# RP2350.net
KiCad netlist of a schematic drawn in Altium Designer
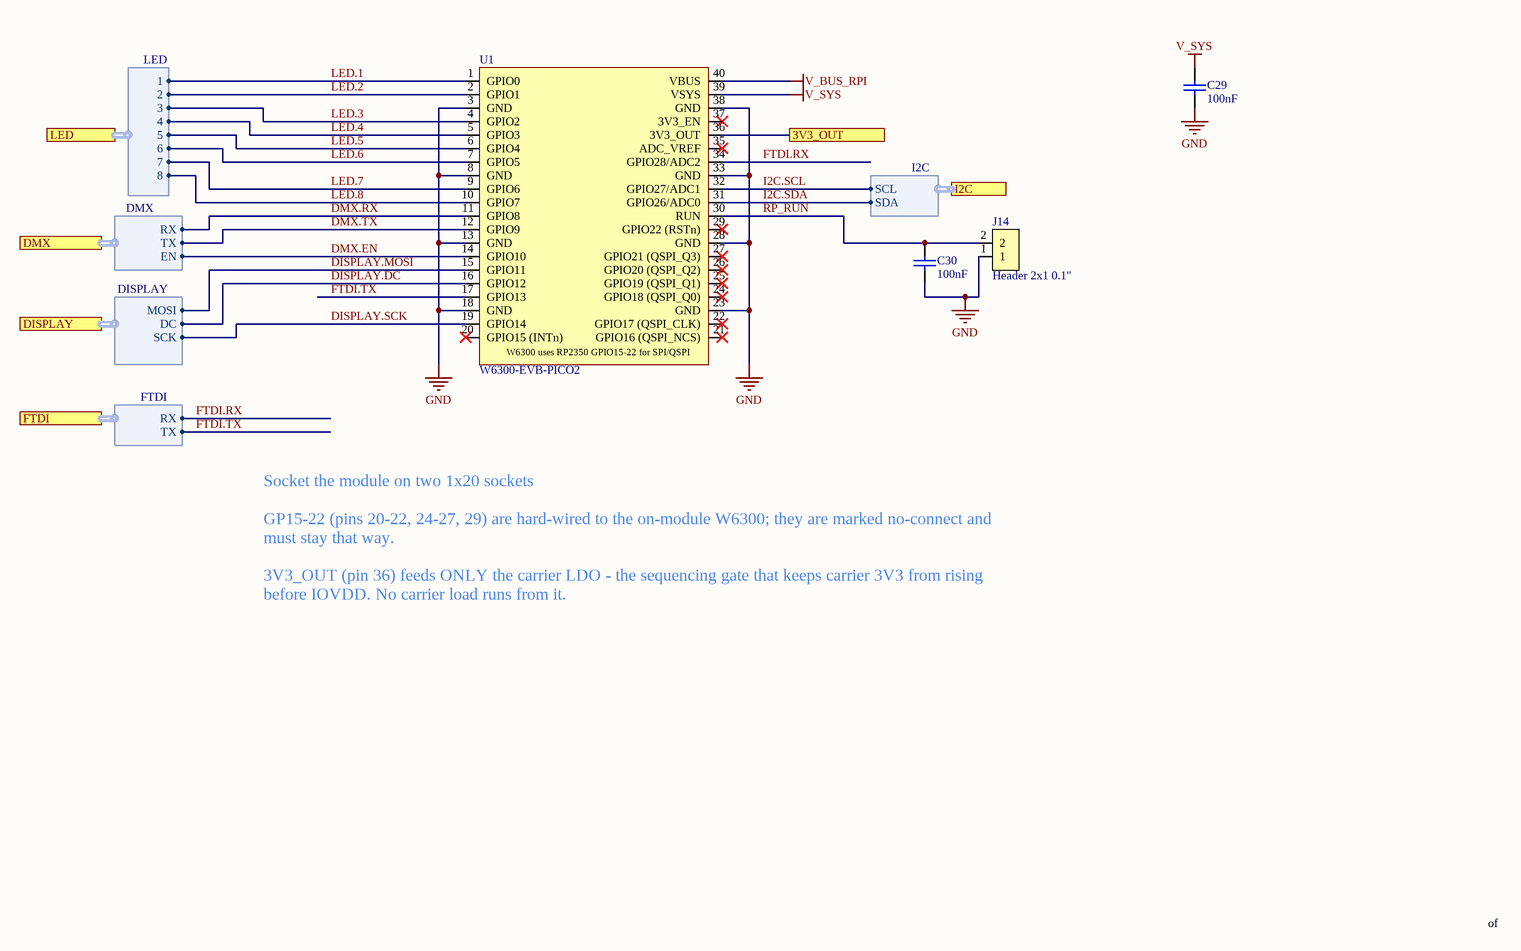
[diagram p0: RP2350.SchDoc]

(export (version "E")
  (design (tool "Eeschema 10.0.6"))
  (components
    (comp (ref "C29")
      (value "100nF")
      (footprint "CAPC1608X10N_0603_MED")
      (fields (field (name "Comment") "CC0603KRX7R0BB104"))
      (libsource (lib "Equus Computer Systems") (part "CAP-NP-2"))
    )
    (comp (ref "C30")
      (value "100nF")
      (footprint "CAPC1608X10N_0603_MED")
      (fields (field (name "Comment") "CC0603KRX7R0BB104"))
      (libsource (lib "Equus Computer Systems") (part "CAP-NP-2"))
    )
    (comp (ref "J14")
      (value "Header 2x1 0.1\"")
      (footprint "FP-M20-9990245-MFG")
      (description "Conn Header Vert 2POS 2.54MM")
      (libsource (lib "Equus Computer Systems") (part "HEADER-2x1"))
    )
    (comp (ref "U1")
      (value "W6300-EVB-PICO2")
      (footprint "W6300-EVB-PICO2_0.4375_standoff")
      (description "Raspberry Pi RP2350 and fully hardwired TCP/IP controller W6300")
      (libsource (lib "Equus Computer Systems") (part "W6300-EVB-PICO2"))
    )
  )
  (nets
    (net (code "6") (name "/3V3_OUT") (class "Default")
      (node (ref "U1") (pin "36") (pinfunction "3V3_OUT_36") (pintype "passive"))
    )
    (net (code "7") (name "/DISPLAY.DC") (class "Default")
      (node (ref "U1") (pin "16") (pinfunction "GPIO12_16") (pintype "passive"))
    )
    (net (code "8") (name "/DISPLAY.MOSI") (class "Default")
      (node (ref "U1") (pin "15") (pinfunction "GPIO11_15") (pintype "passive"))
    )
    (net (code "9") (name "/DISPLAY.SCK") (class "Default")
      (node (ref "U1") (pin "19") (pinfunction "GPIO14_19") (pintype "passive"))
    )
    (net (code "10") (name "/DMX.EN") (class "Default")
      (node (ref "U1") (pin "14") (pinfunction "GPIO10_14") (pintype "passive"))
    )
    (net (code "11") (name "/DMX.RX") (class "Default")
      (node (ref "U1") (pin "11") (pinfunction "GPIO8_11") (pintype "passive"))
    )
    (net (code "12") (name "/DMX.TX") (class "Default")
      (node (ref "U1") (pin "12") (pinfunction "GPIO9_12") (pintype "passive"))
    )
    (net (code "13") (name "/FTDI.RX") (class "Default")
      (node (ref "U1") (pin "34") (pinfunction "GPIO28/ADC2_34") (pintype "passive"))
    )
    (net (code "14") (name "/FTDI.TX") (class "Default")
      (node (ref "U1") (pin "17") (pinfunction "GPIO13_17") (pintype "passive"))
    )
    (net (code "15") (name "/I2C.SCL") (class "Default")
      (node (ref "U1") (pin "32") (pinfunction "GPIO27/ADC1_32") (pintype "passive"))
    )
    (net (code "16") (name "/I2C.SDA") (class "Default")
      (node (ref "U1") (pin "31") (pinfunction "GPIO26/ADC0_31") (pintype "passive"))
    )
    (net (code "17") (name "/LED.1") (class "Default")
      (node (ref "U1") (pin "1") (pinfunction "GPIO0_1") (pintype "passive"))
    )
    (net (code "18") (name "/LED.2") (class "Default")
      (node (ref "U1") (pin "2") (pinfunction "GPIO1_2") (pintype "passive"))
    )
    (net (code "19") (name "/LED.3") (class "Default")
      (node (ref "U1") (pin "4") (pinfunction "GPIO2_4") (pintype "passive"))
    )
    (net (code "20") (name "/LED.4") (class "Default")
      (node (ref "U1") (pin "5") (pinfunction "GPIO3_5") (pintype "passive"))
    )
    (net (code "21") (name "/LED.5") (class "Default")
      (node (ref "U1") (pin "6") (pinfunction "GPIO4_6") (pintype "passive"))
    )
    (net (code "22") (name "/LED.6") (class "Default")
      (node (ref "U1") (pin "7") (pinfunction "GPIO5_7") (pintype "passive"))
    )
    (net (code "23") (name "/LED.7") (class "Default")
      (node (ref "U1") (pin "9") (pinfunction "GPIO6_9") (pintype "passive"))
    )
    (net (code "24") (name "/LED.8") (class "Default")
      (node (ref "U1") (pin "10") (pinfunction "GPIO7_10") (pintype "passive"))
    )
    (net (code "25") (name "/RP_RUN") (class "Default")
      (node (ref "C30") (pin "1") (pinfunction "1_1") (pintype "passive"))
      (node (ref "J14") (pin "2") (pinfunction "2_2") (pintype "passive"))
      (node (ref "U1") (pin "30") (pinfunction "RUN_30") (pintype "passive"))
    )
    (net (code "31") (name "GND") (class "Default")
      (node (ref "C29") (pin "2") (pinfunction "2_2") (pintype "passive"))
      (node (ref "C30") (pin "2") (pinfunction "2_2") (pintype "passive"))
      (node (ref "J14") (pin "1") (pinfunction "1_1") (pintype "passive"))
      (node (ref "U1") (pin "13") (pinfunction "GND_13") (pintype "passive"))
      (node (ref "U1") (pin "18") (pinfunction "GND_18") (pintype "passive"))
      (node (ref "U1") (pin "23") (pinfunction "GND_23") (pintype "passive"))
      (node (ref "U1") (pin "28") (pinfunction "GND_28") (pintype "passive"))
      (node (ref "U1") (pin "3") (pinfunction "GND_3") (pintype "passive"))
      (node (ref "U1") (pin "33") (pinfunction "GND_33") (pintype "passive"))
      (node (ref "U1") (pin "38") (pinfunction "GND_38") (pintype "passive"))
      (node (ref "U1") (pin "8") (pinfunction "GND_8") (pintype "passive"))
    )
    (net (code "32") (name "V_BUS_RPI") (class "Default")
      (node (ref "U1") (pin "40") (pinfunction "VBUS_40") (pintype "passive"))
    )
    (net (code "33") (name "V_SYS") (class "Default")
      (node (ref "C29") (pin "1") (pinfunction "1_1") (pintype "passive"))
      (node (ref "U1") (pin "39") (pinfunction "VSYS_39") (pintype "passive"))
    )
    (net (code "34") (name "unconnected-(U1-3V3_EN-Pad37)") (class "Default")
      (node (ref "U1") (pin "37") (pinfunction "3V3_EN_37") (pintype "passive+no_connect"))
    )
    (net (code "35") (name "unconnected-(U1-ADC_VREF-Pad35)") (class "Default")
      (node (ref "U1") (pin "35") (pinfunction "ADC_VREF_35") (pintype "passive+no_connect"))
    )
    (net (code "36") (name "unconnected-(U1-GPIO15_(INTn)-Pad20)") (class "Default")
      (node (ref "U1") (pin "20") (pinfunction "GPIO15_(INTn)_20") (pintype "passive+no_connect"))
    )
    (net (code "37") (name "unconnected-(U1-GPIO16_(QSPI_NCS)-Pad21)") (class "Default")
      (node (ref "U1") (pin "21") (pinfunction "GPIO16_(QSPI_NCS)_21") (pintype "passive+no_connect"))
    )
    (net (code "38") (name "unconnected-(U1-GPIO17_(QSPI_CLK)-Pad22)") (class "Default")
      (node (ref "U1") (pin "22") (pinfunction "GPIO17_(QSPI_CLK)_22") (pintype "passive+no_connect"))
    )
    (net (code "39") (name "unconnected-(U1-GPIO18_(QSPI_Q0)-Pad24)") (class "Default")
      (node (ref "U1") (pin "24") (pinfunction "GPIO18_(QSPI_Q0)_24") (pintype "passive+no_connect"))
    )
    (net (code "40") (name "unconnected-(U1-GPIO19_(QSPI_Q1)-Pad25)") (class "Default")
      (node (ref "U1") (pin "25") (pinfunction "GPIO19_(QSPI_Q1)_25") (pintype "passive+no_connect"))
    )
    (net (code "41") (name "unconnected-(U1-GPIO20_(QSPI_Q2)-Pad26)") (class "Default")
      (node (ref "U1") (pin "26") (pinfunction "GPIO20_(QSPI_Q2)_26") (pintype "passive+no_connect"))
    )
    (net (code "42") (name "unconnected-(U1-GPIO21_(QSPI_Q3)-Pad27)") (class "Default")
      (node (ref "U1") (pin "27") (pinfunction "GPIO21_(QSPI_Q3)_27") (pintype "passive+no_connect"))
    )
    (net (code "43") (name "unconnected-(U1-GPIO22_(RSTn)-Pad29)") (class "Default")
      (node (ref "U1") (pin "29") (pinfunction "GPIO22_(RSTn)_29") (pintype "passive+no_connect"))
    )
  )
)
